# microcontroller.net
KiCad netlist of a schematic drawn in EAGLE
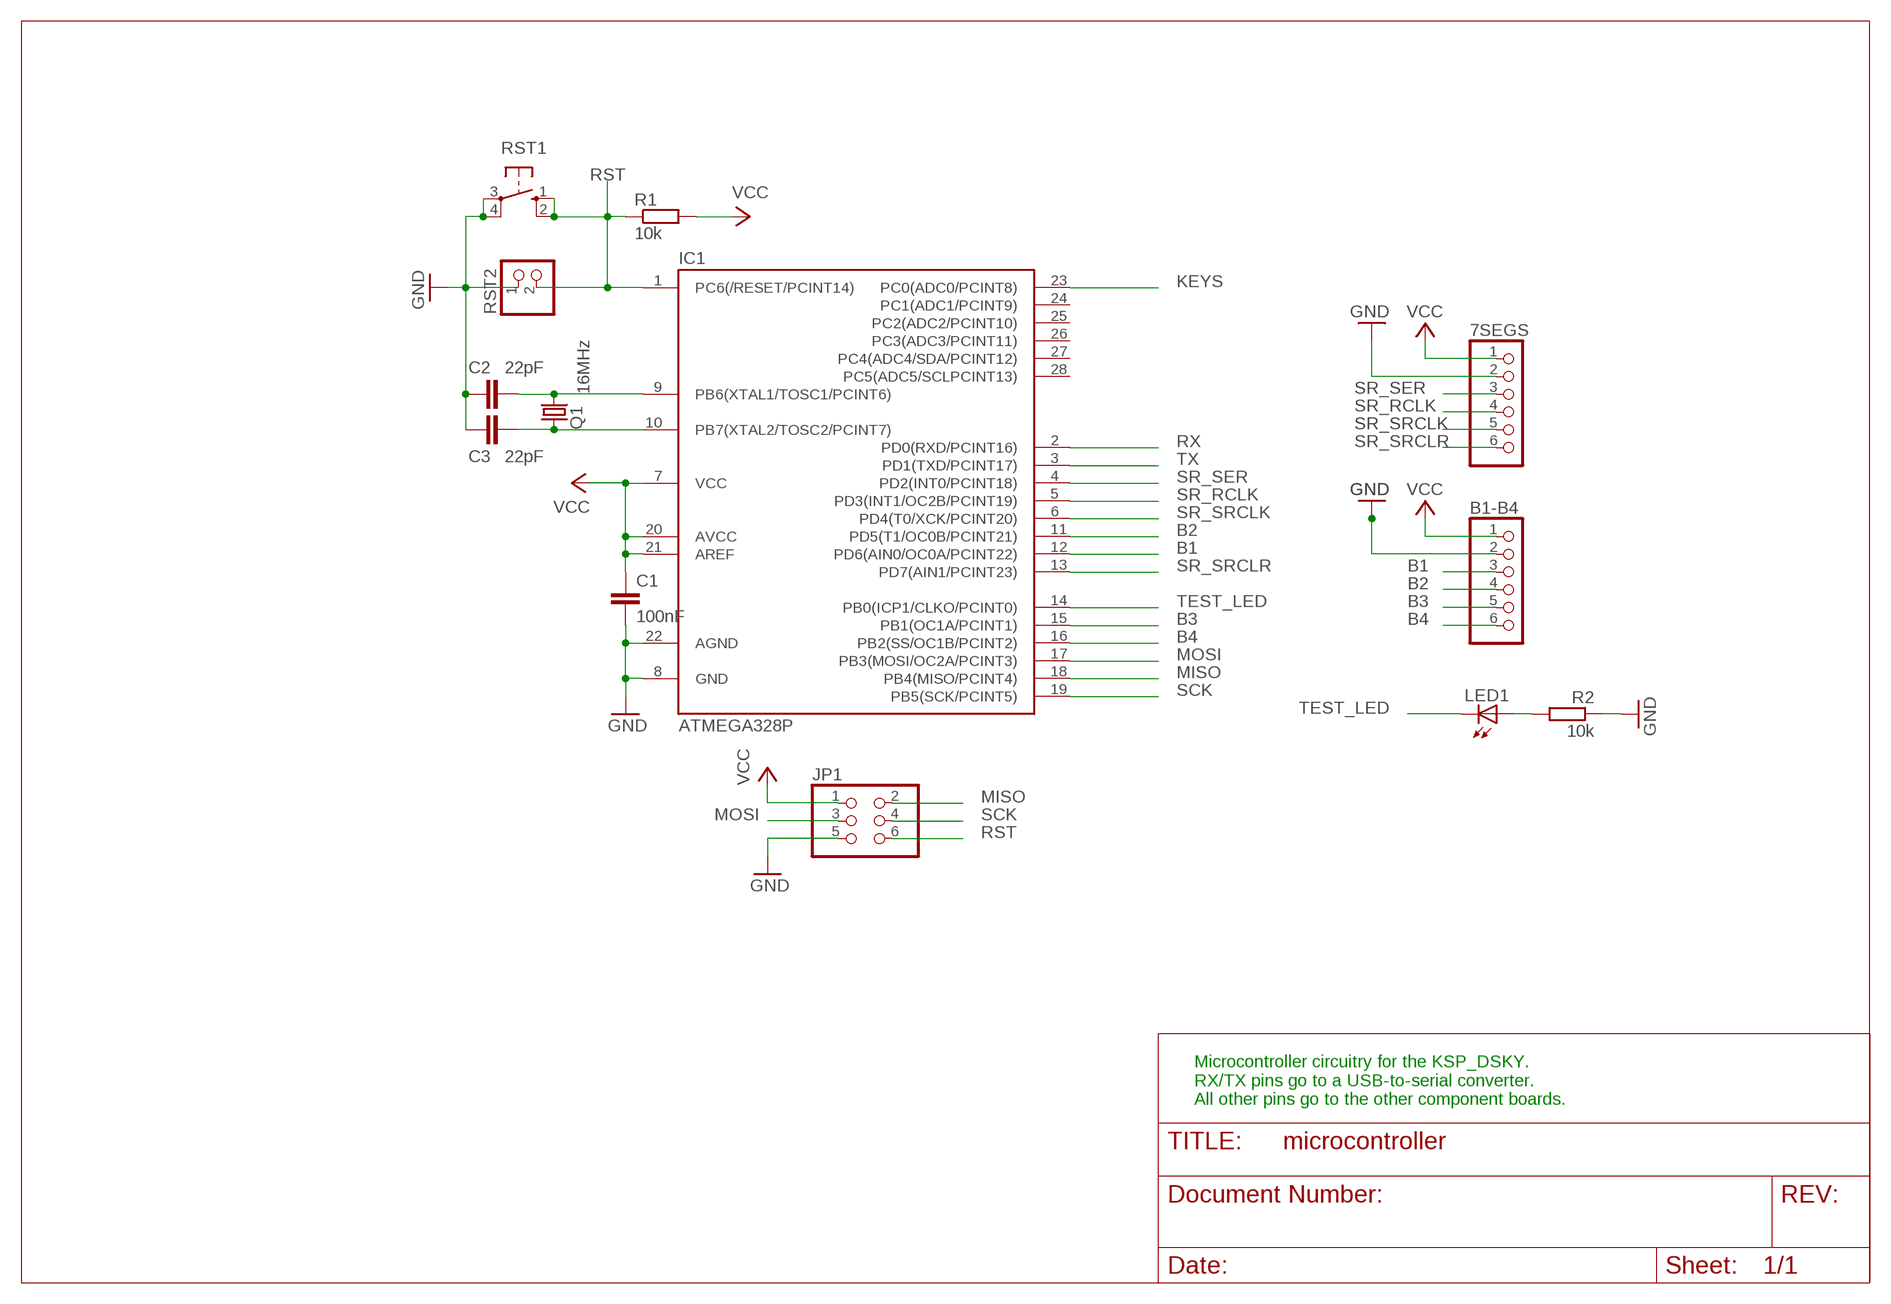
[diagram p0: schematic, sheet 1]

(export (version "E")
  (design (tool "Eeschema 10.0.6"))
  (components
    (comp (ref "7SEGS")
      (value "PINHD-1X6")
      (footprint "eagle-import:1X06")
      (libsource (lib "eagle-import") (part "PINHD-1X6"))
    )
    (comp (ref "B1-B4")
      (value "PINHD-1X6")
      (footprint "eagle-import:1X06")
      (libsource (lib "eagle-import") (part "PINHD-1X6"))
    )
    (comp (ref "C1")
      (value "100nF")
      (footprint "eagle-import:C025-024X044")
      (libsource (lib "eagle-import") (part "C-EU025-024X044"))
    )
    (comp (ref "C2")
      (value "22pF")
      (footprint "eagle-import:C025-024X044")
      (libsource (lib "eagle-import") (part "C-EU025-024X044"))
    )
    (comp (ref "C3")
      (value "22pF")
      (footprint "eagle-import:C025-024X044")
      (libsource (lib "eagle-import") (part "C-EU025-024X044"))
    )
    (comp (ref "IC1")
      (value "ATMEGA328P")
      (footprint "eagle-import:DIL28-3")
      (libsource (lib "eagle-import") (part "MEGA48/88/168-PU"))
    )
    (comp (ref "JP1")
      (value "PINHD-2X3")
      (footprint "eagle-import:2X03")
      (libsource (lib "eagle-import") (part "PINHD-2X3"))
    )
    (comp (ref "LED1")
      (value "LED3MM")
      (footprint "eagle-import:LED3MM")
      (libsource (lib "eagle-import") (part "LED3MM"))
    )
    (comp (ref "Q1")
      (value "16MHz")
      (footprint "eagle-import:HC49U-V")
      (libsource (lib "eagle-import") (part "CRYSTALHC49U-V"))
    )
    (comp (ref "R1")
      (value "10k")
      (footprint "eagle-import:0207_10")
      (libsource (lib "eagle-import") (part "R-EU_0207/10"))
    )
    (comp (ref "R2")
      (value "10k")
      (footprint "eagle-import:0207_10")
      (libsource (lib "eagle-import") (part "R-EU_0207/10"))
    )
    (comp (ref "RST1")
      (value "10-XX")
      (footprint "eagle-import:B3F-10XX")
      (fields (field (name "MPN") "B3F-1000"))
      (libsource (lib "eagle-import") (part "10-XX"))
    )
    (comp (ref "RST2")
      (value "PINHD-1X2")
      (footprint "eagle-import:1X02")
      (libsource (lib "eagle-import") (part "PINHD-1X2"))
    )
  )
  (nets
    (net (code "1") (name "/B1") (class "Default")
      (node (ref "B1-B4") (pin "3") (pinfunction "3_3") (pintype "passive"))
      (node (ref "IC1") (pin "12") (pinfunction "PD6(AIN0/OC0A/PCINT22)_12") (pintype "bidirectional"))
    )
    (net (code "2") (name "/B2") (class "Default")
      (node (ref "B1-B4") (pin "4") (pinfunction "4_4") (pintype "passive"))
      (node (ref "IC1") (pin "11") (pinfunction "PD5(T1/OC0B/PCINT21)_11") (pintype "bidirectional"))
    )
    (net (code "3") (name "/B3") (class "Default")
      (node (ref "B1-B4") (pin "5") (pinfunction "5_5") (pintype "passive"))
      (node (ref "IC1") (pin "15") (pinfunction "PB1(OC1A/PCINT1)_15") (pintype "bidirectional"))
    )
    (net (code "4") (name "/B4") (class "Default")
      (node (ref "B1-B4") (pin "6") (pinfunction "6_6") (pintype "passive"))
      (node (ref "IC1") (pin "16") (pinfunction "PB2(SS/OC1B/PCINT2)_16") (pintype "bidirectional"))
    )
    (net (code "5") (name "/KEYS") (class "Default")
      (node (ref "IC1") (pin "23") (pinfunction "PC0(ADC0/PCINT8)_23") (pintype "bidirectional"))
    )
    (net (code "6") (name "/MISO") (class "Default")
      (node (ref "IC1") (pin "18") (pinfunction "PB4(MISO/PCINT4)_18") (pintype "bidirectional"))
      (node (ref "JP1") (pin "2") (pinfunction "2_2") (pintype "passive"))
    )
    (net (code "7") (name "/MOSI") (class "Default")
      (node (ref "IC1") (pin "17") (pinfunction "PB3(MOSI/OC2A/PCINT3)_17") (pintype "bidirectional"))
      (node (ref "JP1") (pin "3") (pinfunction "3_3") (pintype "passive"))
    )
    (net (code "8") (name "/RST") (class "Default")
      (node (ref "IC1") (pin "1") (pinfunction "PC6(/RESET/PCINT14)_1") (pintype "bidirectional"))
      (node (ref "JP1") (pin "6") (pinfunction "6_6") (pintype "passive"))
      (node (ref "R1") (pin "1") (pinfunction "1_1") (pintype "passive"))
      (node (ref "RST1") (pin "1") (pinfunction "S_1") (pintype "passive"))
      (node (ref "RST1") (pin "2") (pinfunction "S1_2") (pintype "passive"))
      (node (ref "RST2") (pin "2") (pinfunction "2_2") (pintype "passive"))
    )
    (net (code "9") (name "/RX") (class "Default")
      (node (ref "IC1") (pin "2") (pinfunction "PD0(RXD/PCINT16)_2") (pintype "bidirectional"))
    )
    (net (code "10") (name "/SCK") (class "Default")
      (node (ref "IC1") (pin "19") (pinfunction "PB5(SCK/PCINT5)_19") (pintype "bidirectional"))
      (node (ref "JP1") (pin "4") (pinfunction "4_4") (pintype "passive"))
    )
    (net (code "11") (name "/SR_RCLK") (class "Default")
      (node (ref "7SEGS") (pin "4") (pinfunction "4_4") (pintype "passive"))
      (node (ref "IC1") (pin "5") (pinfunction "PD3(INT1/OC2B/PCINT19)_5") (pintype "bidirectional"))
    )
    (net (code "12") (name "/SR_SER") (class "Default")
      (node (ref "7SEGS") (pin "3") (pinfunction "3_3") (pintype "passive"))
      (node (ref "IC1") (pin "4") (pinfunction "PD2(INT0/PCINT18)_4") (pintype "bidirectional"))
    )
    (net (code "13") (name "/SR_SRCLK") (class "Default")
      (node (ref "7SEGS") (pin "5") (pinfunction "5_5") (pintype "passive"))
      (node (ref "IC1") (pin "6") (pinfunction "PD4(T0/XCK/PCINT20)_6") (pintype "bidirectional"))
    )
    (net (code "14") (name "/SR_SRCLR") (class "Default")
      (node (ref "7SEGS") (pin "6") (pinfunction "6_6") (pintype "passive"))
      (node (ref "IC1") (pin "13") (pinfunction "PD7(AIN1/PCINT23)_13") (pintype "bidirectional"))
    )
    (net (code "15") (name "/TEST_LED") (class "Default")
      (node (ref "IC1") (pin "14") (pinfunction "PB0(ICP1/CLKO/PCINT0)_14") (pintype "bidirectional"))
      (node (ref "LED1") (pin "K") (pinfunction "C_K") (pintype "passive"))
    )
    (net (code "16") (name "/TX") (class "Default")
      (node (ref "IC1") (pin "3") (pinfunction "PD1(TXD/PCINT17)_3") (pintype "bidirectional"))
    )
    (net (code "17") (name "GND") (class "Default")
      (node (ref "7SEGS") (pin "2") (pinfunction "2_2") (pintype "passive"))
      (node (ref "B1-B4") (pin "2") (pinfunction "2_2") (pintype "passive"))
      (node (ref "C1") (pin "2") (pinfunction "2_2") (pintype "passive"))
      (node (ref "C2") (pin "1") (pinfunction "1_1") (pintype "passive"))
      (node (ref "C3") (pin "1") (pinfunction "1_1") (pintype "passive"))
      (node (ref "IC1") (pin "22") (pinfunction "AGND_22") (pintype "power_in"))
      (node (ref "IC1") (pin "8") (pinfunction "GND_8") (pintype "power_in"))
      (node (ref "JP1") (pin "5") (pinfunction "5_5") (pintype "passive"))
      (node (ref "R2") (pin "1") (pinfunction "1_1") (pintype "passive"))
      (node (ref "RST1") (pin "3") (pinfunction "P_3") (pintype "passive"))
      (node (ref "RST1") (pin "4") (pinfunction "P1_4") (pintype "passive"))
      (node (ref "RST2") (pin "1") (pinfunction "1_1") (pintype "passive"))
    )
    (net (code "18") (name "Net-(IC1-PB6(XTAL1{slash}TOSC1{slash}PCINT6))") (class "Default")
      (node (ref "C2") (pin "2") (pinfunction "2_2") (pintype "passive"))
      (node (ref "IC1") (pin "9") (pinfunction "PB6(XTAL1/TOSC1/PCINT6)_9") (pintype "bidirectional"))
      (node (ref "Q1") (pin "2") (pinfunction "2_2") (pintype "passive"))
    )
    (net (code "19") (name "Net-(IC1-PB7(XTAL2{slash}TOSC2{slash}PCINT7))") (class "Default")
      (node (ref "C3") (pin "2") (pinfunction "2_2") (pintype "passive"))
      (node (ref "IC1") (pin "10") (pinfunction "PB7(XTAL2/TOSC2/PCINT7)_10") (pintype "bidirectional"))
      (node (ref "Q1") (pin "1") (pinfunction "1_1") (pintype "passive"))
    )
    (net (code "20") (name "Net-(LED1-PadA)") (class "Default")
      (node (ref "LED1") (pin "A") (pinfunction "A_A") (pintype "passive"))
      (node (ref "R2") (pin "2") (pinfunction "2_2") (pintype "passive"))
    )
    (net (code "21") (name "VCC") (class "Default")
      (node (ref "7SEGS") (pin "1") (pinfunction "1_1") (pintype "passive"))
      (node (ref "B1-B4") (pin "1") (pinfunction "1_1") (pintype "passive"))
      (node (ref "C1") (pin "1") (pinfunction "1_1") (pintype "passive"))
      (node (ref "IC1") (pin "20") (pinfunction "AVCC_20") (pintype "passive"))
      (node (ref "IC1") (pin "21") (pinfunction "AREF_21") (pintype "passive"))
      (node (ref "IC1") (pin "7") (pinfunction "VCC_7") (pintype "power_in"))
      (node (ref "JP1") (pin "1") (pinfunction "1_1") (pintype "passive"))
      (node (ref "R1") (pin "2") (pinfunction "2_2") (pintype "passive"))
    )
    (net (code "22") (name "unconnected-(IC1-PC1(ADC1{slash}PCINT9)-Pad24)") (class "Default")
      (node (ref "IC1") (pin "24") (pinfunction "PC1(ADC1/PCINT9)_24") (pintype "bidirectional"))
    )
    (net (code "23") (name "unconnected-(IC1-PC2(ADC2{slash}PCINT10)-Pad25)") (class "Default")
      (node (ref "IC1") (pin "25") (pinfunction "PC2(ADC2/PCINT10)_25") (pintype "bidirectional"))
    )
    (net (code "24") (name "unconnected-(IC1-PC3(ADC3{slash}PCINT11)-Pad26)") (class "Default")
      (node (ref "IC1") (pin "26") (pinfunction "PC3(ADC3/PCINT11)_26") (pintype "bidirectional"))
    )
    (net (code "25") (name "unconnected-(IC1-PC4(ADC4{slash}SDA{slash}PCINT12)-Pad27)") (class "Default")
      (node (ref "IC1") (pin "27") (pinfunction "PC4(ADC4/SDA/PCINT12)_27") (pintype "bidirectional"))
    )
    (net (code "26") (name "unconnected-(IC1-PC5(ADC5{slash}SCLPCINT13)-Pad28)") (class "Default")
      (node (ref "IC1") (pin "28") (pinfunction "PC5(ADC5/SCLPCINT13)_28") (pintype "bidirectional"))
    )
  )
)
